# ControlBoard.net
KiCad netlist of a schematic drawn in EAGLE
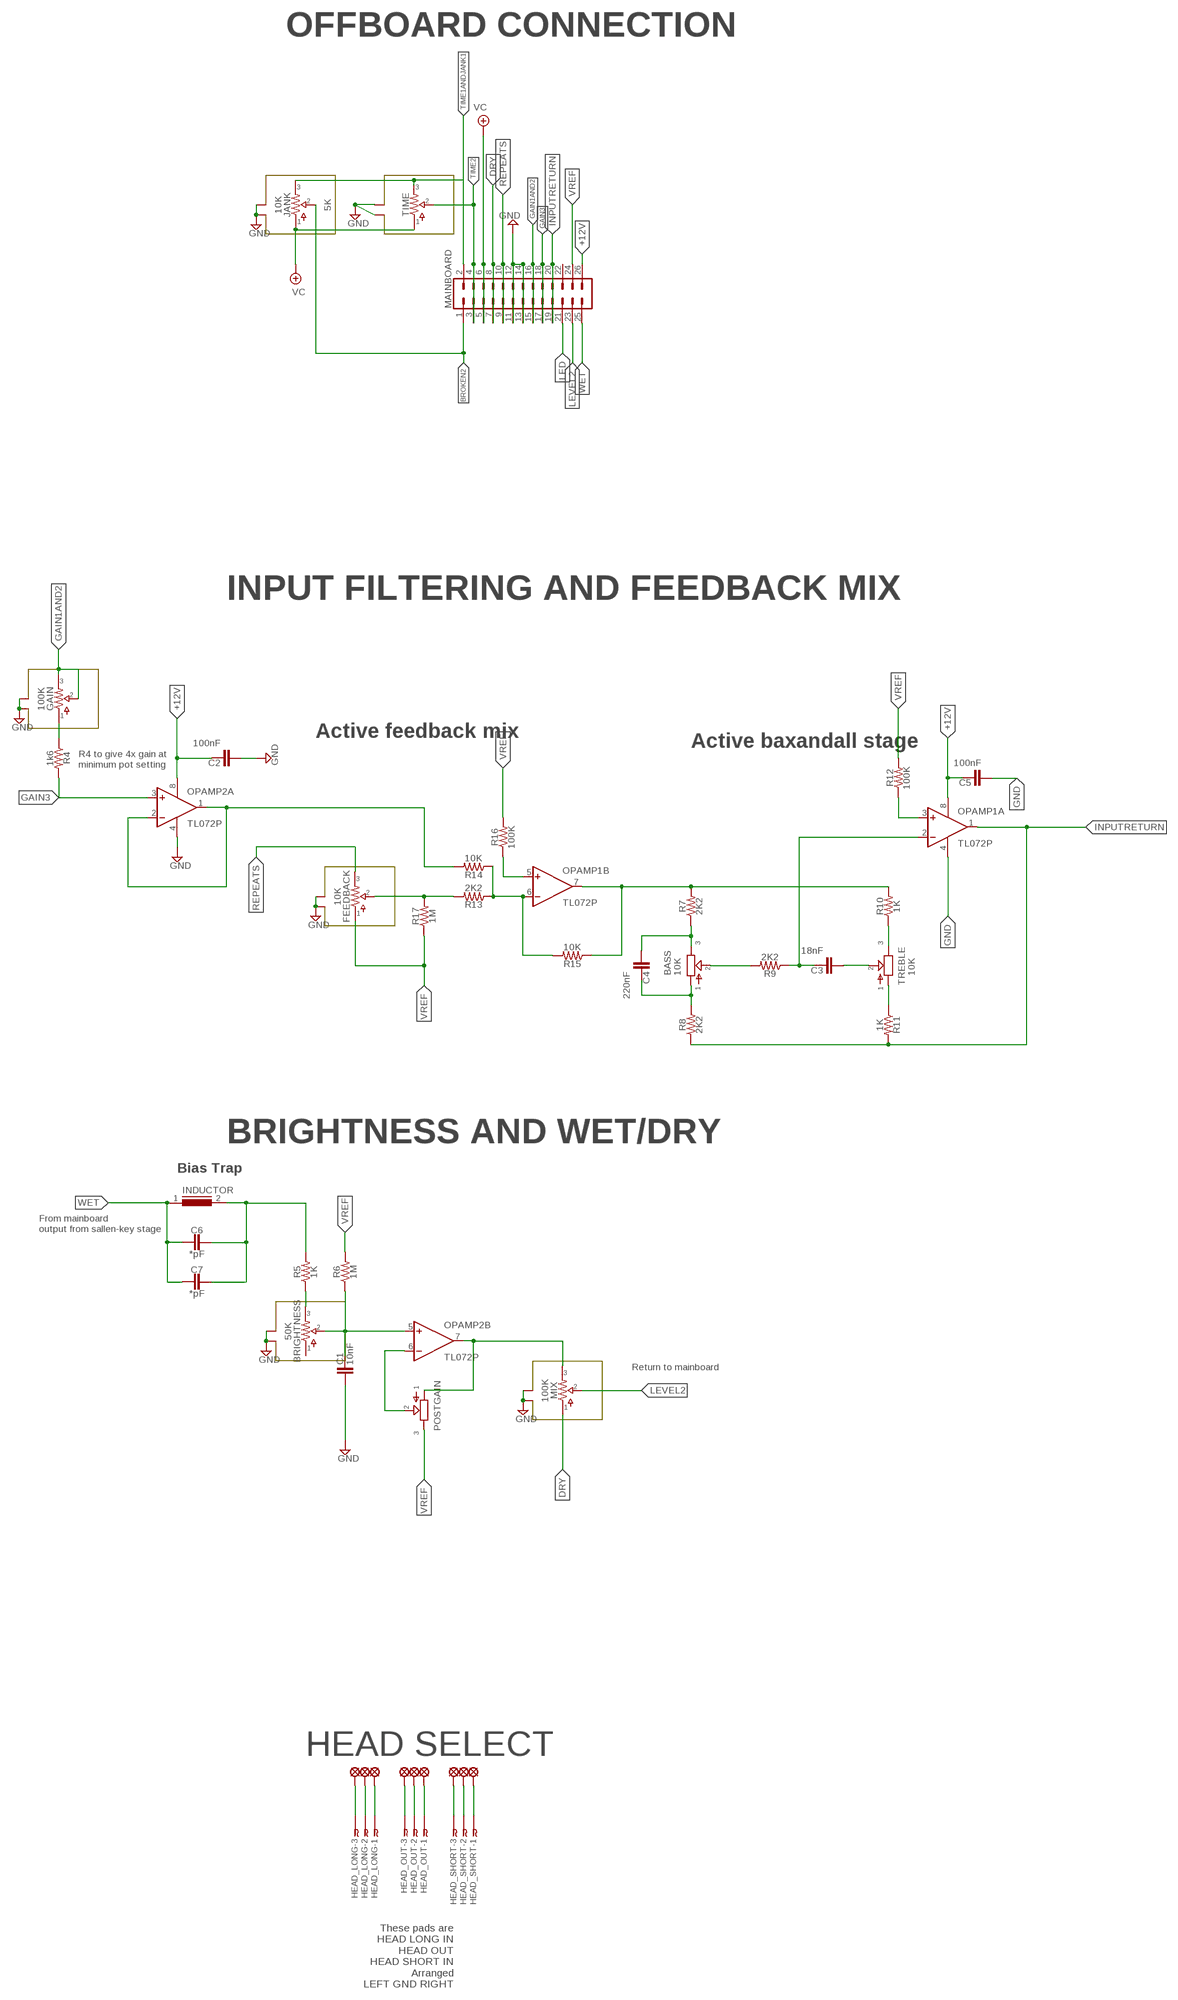
[diagram p0: schematic, sheet 1]

(export (version "E")
  (design (tool "Eeschema 10.0.6"))
  (components
    (comp (ref "BASS")
      (value "10K")
      (footprint "eagle-import:B375P")
      (libsource (lib "eagle-import") (part "POT-EU375"))
    )
    (comp (ref "BRIGHTNESS")
      (value "50K")
      (footprint "eagle-import:9MM_METAL_SHAFT")
      (libsource (lib "eagle-import") (part "9MM.1"))
    )
    (comp (ref "C1")
      (value "10nF")
      (footprint "eagle-import:.33UF+")
      (libsource (lib "eagle-import") (part "CAP.5"))
    )
    (comp (ref "C2")
      (value "100nF")
      (footprint "eagle-import:5MM")
      (libsource (lib "eagle-import") (part "CAP.2"))
    )
    (comp (ref "C3")
      (value "18nF")
      (footprint "eagle-import:.33UF+")
      (libsource (lib "eagle-import") (part "CAP.5"))
    )
    (comp (ref "C4")
      (value "220nF")
      (footprint "eagle-import:.33UF+")
      (libsource (lib "eagle-import") (part "CAP.5"))
    )
    (comp (ref "C5")
      (value "100nF")
      (footprint "eagle-import:5MM")
      (libsource (lib "eagle-import") (part "CAP.2"))
    )
    (comp (ref "C6")
      (value "*pF")
      (footprint "eagle-import:.33UF+")
      (libsource (lib "eagle-import") (part "CAP.5"))
    )
    (comp (ref "C7")
      (value "*pF")
      (footprint "eagle-import:.33UF+")
      (libsource (lib "eagle-import") (part "CAP.5"))
    )
    (comp (ref "FEEDBACK")
      (value "10K")
      (footprint "eagle-import:9MM_METAL_SHAFT")
      (libsource (lib "eagle-import") (part "9MM.1"))
    )
    (comp (ref "GAIN")
      (value "100K")
      (footprint "eagle-import:9MM_METAL_SHAFT")
      (libsource (lib "eagle-import") (part "9MM.1"))
    )
    (comp (ref "HEAD_LONG")
      (value "03-JST-B3B-XH-A")
      (footprint "eagle-import:B3B-XH")
      (libsource (lib "eagle-import") (part "03-JST-B3B-XH-A"))
    )
    (comp (ref "HEAD_OUT")
      (value "03-JST-B3B-XH-A")
      (footprint "eagle-import:B3B-XH")
      (libsource (lib "eagle-import") (part "03-JST-B3B-XH-A"))
    )
    (comp (ref "HEAD_SHORT")
      (value "03-JST-B3B-XH-A")
      (footprint "eagle-import:B3B-XH")
      (libsource (lib "eagle-import") (part "03-JST-B3B-XH-A"))
    )
    (comp (ref "HIN_1")
      (value "SE14")
      (footprint "eagle-import:SE14")
      (libsource (lib "eagle-import") (part "SE14"))
    )
    (comp (ref "HIN_2")
      (value "SE14")
      (footprint "eagle-import:SE14")
      (libsource (lib "eagle-import") (part "SE14"))
    )
    (comp (ref "HIN_3")
      (value "SE14")
      (footprint "eagle-import:SE14")
      (libsource (lib "eagle-import") (part "SE14"))
    )
    (comp (ref "HIN_4")
      (value "SE14")
      (footprint "eagle-import:SE14")
      (libsource (lib "eagle-import") (part "SE14"))
    )
    (comp (ref "HIN_5")
      (value "SE14")
      (footprint "eagle-import:SE14")
      (libsource (lib "eagle-import") (part "SE14"))
    )
    (comp (ref "HIN_6")
      (value "SE14")
      (footprint "eagle-import:SE14")
      (libsource (lib "eagle-import") (part "SE14"))
    )
    (comp (ref "HOUT_1")
      (value "SE14")
      (footprint "eagle-import:SE14")
      (libsource (lib "eagle-import") (part "SE14"))
    )
    (comp (ref "HOUT_2")
      (value "SE14")
      (footprint "eagle-import:SE14")
      (libsource (lib "eagle-import") (part "SE14"))
    )
    (comp (ref "HOUT_3")
      (value "SE14")
      (footprint "eagle-import:SE14")
      (libsource (lib "eagle-import") (part "SE14"))
    )
    (comp (ref "INDUCTOR")
      (value "82114R")
      (footprint "eagle-import:82114R")
      (libsource (lib "eagle-import") (part "82114R"))
    )
    (comp (ref "JANK")
      (value "10K")
      (footprint "eagle-import:9MM_METAL_SHAFT")
      (libsource (lib "eagle-import") (part "9MM.1"))
    )
    (comp (ref "MAINBOARD")
      (value "CONN_13X22X13")
      (footprint "eagle-import:2X13")
      (libsource (lib "eagle-import") (part "CONN_13X22X13"))
    )
    (comp (ref "MIX")
      (value "100K")
      (footprint "eagle-import:9MM_METAL_SHAFT")
      (libsource (lib "eagle-import") (part "9MM.1"))
    )
    (comp (ref "OPAMP1")
      (value "TL072P")
      (footprint "eagle-import:DIL08")
      (libsource (lib "eagle-import") (part "TL072P"))
    )
    (comp (ref "OPAMP2")
      (value "TL072P")
      (footprint "eagle-import:DIL08")
      (libsource (lib "eagle-import") (part "TL072P"))
    )
    (comp (ref "POSTGAIN")
      (value "POT-EU375")
      (footprint "eagle-import:B375P")
      (libsource (lib "eagle-import") (part "POT-EU375"))
    )
    (comp (ref "R4")
      (value "1k6")
      (footprint "eagle-import:7.5MM.2")
      (libsource (lib "eagle-import") (part "R.3B"))
    )
    (comp (ref "R5")
      (value "1K")
      (footprint "eagle-import:7.5MM.2")
      (libsource (lib "eagle-import") (part "R.3B"))
    )
    (comp (ref "R6")
      (value "1M")
      (footprint "eagle-import:7.5MM.2")
      (libsource (lib "eagle-import") (part "R.3B"))
    )
    (comp (ref "R7")
      (value "2K2")
      (footprint "eagle-import:7.5MM.2")
      (libsource (lib "eagle-import") (part "R.3B"))
    )
    (comp (ref "R8")
      (value "2K2")
      (footprint "eagle-import:7.5MM.2")
      (libsource (lib "eagle-import") (part "R.3B"))
    )
    (comp (ref "R9")
      (value "2K2")
      (footprint "eagle-import:7.5MM.2")
      (libsource (lib "eagle-import") (part "R.3B"))
    )
    (comp (ref "R10")
      (value "1K")
      (footprint "eagle-import:7.5MM.2")
      (libsource (lib "eagle-import") (part "R.3B"))
    )
    (comp (ref "R11")
      (value "1K")
      (footprint "eagle-import:7.5MM.2")
      (libsource (lib "eagle-import") (part "R.3B"))
    )
    (comp (ref "R12")
      (value "100K")
      (footprint "eagle-import:7.5MM.2")
      (libsource (lib "eagle-import") (part "R.3B"))
    )
    (comp (ref "R13")
      (value "2K2")
      (footprint "eagle-import:7.5MM.2")
      (libsource (lib "eagle-import") (part "R.3B"))
    )
    (comp (ref "R14")
      (value "10K")
      (footprint "eagle-import:7.5MM.2")
      (libsource (lib "eagle-import") (part "R.3B"))
    )
    (comp (ref "R15")
      (value "10K")
      (footprint "eagle-import:7.5MM.2")
      (libsource (lib "eagle-import") (part "R.3B"))
    )
    (comp (ref "R16")
      (value "100K")
      (footprint "eagle-import:7.5MM.2")
      (libsource (lib "eagle-import") (part "R.3B"))
    )
    (comp (ref "R17")
      (value "1M")
      (footprint "eagle-import:7.5MM.2")
      (libsource (lib "eagle-import") (part "R.3B"))
    )
    (comp (ref "TIME")
      (value "5K")
      (footprint "eagle-import:9MM_METAL_SHAFT")
      (libsource (lib "eagle-import") (part "9MM.1"))
    )
    (comp (ref "TREBLE")
      (value "10K")
      (footprint "eagle-import:B375P")
      (libsource (lib "eagle-import") (part "POT-EU375"))
    )
  )
  (nets
    (net (code "1") (name "+12V") (class "Default")
      (node (ref "C2") (pin "1") (pinfunction "1_1") (pintype "passive"))
      (node (ref "C5") (pin "1") (pinfunction "1_1") (pintype "passive"))
      (node (ref "MAINBOARD") (pin "26") (pinfunction "26_26") (pintype "passive"))
      (node (ref "OPAMP1") (pin "8") (pinfunction "V+_8") (pintype "power_in"))
      (node (ref "OPAMP2") (pin "8") (pinfunction "V+_8") (pintype "power_in"))
    )
    (net (code "2") (name "BROKEN2") (class "Default")
      (node (ref "JANK") (pin "P$2") (pinfunction "2_P$2") (pintype "passive"))
      (node (ref "MAINBOARD") (pin "1") (pinfunction "1_1") (pintype "passive"))
    )
    (net (code "3") (name "DRY") (class "Default")
      (node (ref "MAINBOARD") (pin "7") (pinfunction "7_7") (pintype "passive"))
      (node (ref "MAINBOARD") (pin "8") (pinfunction "8_8") (pintype "passive"))
      (node (ref "MIX") (pin "P$1") (pinfunction "1_P$1") (pintype "passive"))
    )
    (net (code "4") (name "GAIN1AND2") (class "Default")
      (node (ref "GAIN") (pin "P$2") (pinfunction "2_P$2") (pintype "passive"))
      (node (ref "GAIN") (pin "P$3") (pinfunction "3_P$3") (pintype "passive"))
      (node (ref "MAINBOARD") (pin "15") (pinfunction "15_15") (pintype "passive"))
      (node (ref "MAINBOARD") (pin "16") (pinfunction "16_16") (pintype "passive"))
    )
    (net (code "5") (name "GAIN3") (class "Default")
      (node (ref "MAINBOARD") (pin "17") (pinfunction "17_17") (pintype "passive"))
      (node (ref "MAINBOARD") (pin "18") (pinfunction "18_18") (pintype "passive"))
      (node (ref "OPAMP2") (pin "3") (pinfunction "+IN_3") (pintype "input"))
      (node (ref "R4") (pin "2") (pinfunction "2_2") (pintype "passive"))
    )
    (net (code "6") (name "GND") (class "Default")
      (node (ref "BRIGHTNESS") (pin "P$4") (pinfunction "CHAS$1_P$4") (pintype "bidirectional"))
      (node (ref "BRIGHTNESS") (pin "P$5") (pinfunction "CHAS$2_P$5") (pintype "bidirectional"))
      (node (ref "C1") (pin "2") (pinfunction "2_2") (pintype "passive"))
      (node (ref "C2") (pin "2") (pinfunction "2_2") (pintype "passive"))
      (node (ref "C5") (pin "2") (pinfunction "2_2") (pintype "passive"))
      (node (ref "FEEDBACK") (pin "P$4") (pinfunction "CHAS$1_P$4") (pintype "bidirectional"))
      (node (ref "FEEDBACK") (pin "P$5") (pinfunction "CHAS$2_P$5") (pintype "bidirectional"))
      (node (ref "GAIN") (pin "P$4") (pinfunction "CHAS$1_P$4") (pintype "bidirectional"))
      (node (ref "GAIN") (pin "P$5") (pinfunction "CHAS$2_P$5") (pintype "bidirectional"))
      (node (ref "JANK") (pin "P$4") (pinfunction "CHAS$1_P$4") (pintype "bidirectional"))
      (node (ref "JANK") (pin "P$5") (pinfunction "CHAS$2_P$5") (pintype "bidirectional"))
      (node (ref "MAINBOARD") (pin "11") (pinfunction "11_11") (pintype "passive"))
      (node (ref "MAINBOARD") (pin "12") (pinfunction "12_12") (pintype "passive"))
      (node (ref "MAINBOARD") (pin "13") (pinfunction "13_13") (pintype "passive"))
      (node (ref "MAINBOARD") (pin "14") (pinfunction "14_14") (pintype "passive"))
      (node (ref "MIX") (pin "P$4") (pinfunction "CHAS$1_P$4") (pintype "bidirectional"))
      (node (ref "MIX") (pin "P$5") (pinfunction "CHAS$2_P$5") (pintype "bidirectional"))
      (node (ref "OPAMP1") (pin "4") (pinfunction "V-_4") (pintype "power_in"))
      (node (ref "OPAMP2") (pin "4") (pinfunction "V-_4") (pintype "power_in"))
      (node (ref "TIME") (pin "P$4") (pinfunction "CHAS$1_P$4") (pintype "bidirectional"))
      (node (ref "TIME") (pin "P$5") (pinfunction "CHAS$2_P$5") (pintype "bidirectional"))
    )
    (net (code "7") (name "INPUTRETURN") (class "Default")
      (node (ref "MAINBOARD") (pin "19") (pinfunction "19_19") (pintype "passive"))
      (node (ref "MAINBOARD") (pin "20") (pinfunction "20_20") (pintype "passive"))
      (node (ref "OPAMP1") (pin "1") (pinfunction "OUT_1") (pintype "output"))
      (node (ref "R11") (pin "2") (pinfunction "2_2") (pintype "passive"))
      (node (ref "R8") (pin "1") (pinfunction "1_1") (pintype "passive"))
    )
    (net (code "8") (name "LED") (class "Default")
      (node (ref "MAINBOARD") (pin "21") (pinfunction "21_21") (pintype "passive"))
    )
    (net (code "9") (name "LEVEL2") (class "Default")
      (node (ref "MAINBOARD") (pin "23") (pinfunction "23_23") (pintype "passive"))
      (node (ref "MIX") (pin "P$2") (pinfunction "2_P$2") (pintype "passive"))
    )
    (net (code "10") (name "Net-(BASS-Pad1)") (class "Default")
      (node (ref "BASS") (pin "1") (pinfunction "1_1") (pintype "passive"))
      (node (ref "C4") (pin "1") (pinfunction "1_1") (pintype "passive"))
      (node (ref "R8") (pin "2") (pinfunction "2_2") (pintype "passive"))
    )
    (net (code "11") (name "Net-(BASS-Pad2)") (class "Default")
      (node (ref "BASS") (pin "2") (pinfunction "2_2") (pintype "passive"))
      (node (ref "R9") (pin "2") (pinfunction "2_2") (pintype "passive"))
    )
    (net (code "12") (name "Net-(BASS-Pad3)") (class "Default")
      (node (ref "BASS") (pin "3") (pinfunction "3_3") (pintype "passive"))
      (node (ref "C4") (pin "2") (pinfunction "2_2") (pintype "passive"))
      (node (ref "R7") (pin "1") (pinfunction "1_1") (pintype "passive"))
    )
    (net (code "13") (name "Net-(BRIGHTNESS-2)") (class "Default")
      (node (ref "BRIGHTNESS") (pin "P$2") (pinfunction "2_P$2") (pintype "passive"))
      (node (ref "C1") (pin "1") (pinfunction "1_1") (pintype "passive"))
      (node (ref "OPAMP2") (pin "5") (pinfunction "+IN_5") (pintype "input"))
      (node (ref "R6") (pin "1") (pinfunction "1_1") (pintype "passive"))
    )
    (net (code "14") (name "Net-(BRIGHTNESS-3)") (class "Default")
      (node (ref "BRIGHTNESS") (pin "P$3") (pinfunction "3_P$3") (pintype "passive"))
      (node (ref "R5") (pin "1") (pinfunction "1_1") (pintype "passive"))
    )
    (net (code "15") (name "Net-(C3-Pad2)") (class "Default")
      (node (ref "C3") (pin "2") (pinfunction "2_2") (pintype "passive"))
      (node (ref "TREBLE") (pin "2") (pinfunction "2_2") (pintype "passive"))
    )
    (net (code "16") (name "Net-(C6-Pad1)") (class "Default")
      (node (ref "C6") (pin "1") (pinfunction "1_1") (pintype "passive"))
      (node (ref "C7") (pin "1") (pinfunction "1_1") (pintype "passive"))
      (node (ref "INDUCTOR") (pin "2") (pinfunction "2_2") (pintype "passive"))
      (node (ref "R5") (pin "2") (pinfunction "2_2") (pintype "passive"))
    )
    (net (code "17") (name "Net-(FEEDBACK-2)") (class "Default")
      (node (ref "FEEDBACK") (pin "P$2") (pinfunction "2_P$2") (pintype "passive"))
      (node (ref "R13") (pin "2") (pinfunction "2_2") (pintype "passive"))
      (node (ref "R17") (pin "2") (pinfunction "2_2") (pintype "passive"))
    )
    (net (code "18") (name "Net-(GAIN-1)") (class "Default")
      (node (ref "GAIN") (pin "P$1") (pinfunction "1_P$1") (pintype "passive"))
      (node (ref "R4") (pin "1") (pinfunction "1_1") (pintype "passive"))
    )
    (net (code "19") (name "Net-(HEAD_LONGA-1)") (class "Default")
      (node (ref "HEAD_LONG") (pin "P$1") (pinfunction "1_P$1") (pintype "passive"))
      (node (ref "HIN_6") (pin "MP") (pinfunction "MP_MP") (pintype "passive"))
    )
    (net (code "20") (name "Net-(HEAD_LONGB-1)") (class "Default")
      (node (ref "HEAD_LONG") (pin "P$2") (pinfunction "1_P$2") (pintype "passive"))
      (node (ref "HIN_5") (pin "MP") (pinfunction "MP_MP") (pintype "passive"))
    )
    (net (code "21") (name "Net-(HEAD_LONGC-1)") (class "Default")
      (node (ref "HEAD_LONG") (pin "P$3") (pinfunction "1_P$3") (pintype "passive"))
      (node (ref "HIN_4") (pin "MP") (pinfunction "MP_MP") (pintype "passive"))
    )
    (net (code "22") (name "Net-(HEAD_OUTA-1)") (class "Default")
      (node (ref "HEAD_OUT") (pin "P$1") (pinfunction "1_P$1") (pintype "passive"))
      (node (ref "HOUT_3") (pin "MP") (pinfunction "MP_MP") (pintype "passive"))
    )
    (net (code "23") (name "Net-(HEAD_OUTB-1)") (class "Default")
      (node (ref "HEAD_OUT") (pin "P$2") (pinfunction "1_P$2") (pintype "passive"))
      (node (ref "HOUT_2") (pin "MP") (pinfunction "MP_MP") (pintype "passive"))
    )
    (net (code "24") (name "Net-(HEAD_OUTC-1)") (class "Default")
      (node (ref "HEAD_OUT") (pin "P$3") (pinfunction "1_P$3") (pintype "passive"))
      (node (ref "HOUT_1") (pin "MP") (pinfunction "MP_MP") (pintype "passive"))
    )
    (net (code "25") (name "Net-(HEAD_SHORTA-1)") (class "Default")
      (node (ref "HEAD_SHORT") (pin "P$1") (pinfunction "1_P$1") (pintype "passive"))
      (node (ref "HIN_3") (pin "MP") (pinfunction "MP_MP") (pintype "passive"))
    )
    (net (code "26") (name "Net-(HEAD_SHORTB-1)") (class "Default")
      (node (ref "HEAD_SHORT") (pin "P$2") (pinfunction "1_P$2") (pintype "passive"))
      (node (ref "HIN_2") (pin "MP") (pinfunction "MP_MP") (pintype "passive"))
    )
    (net (code "27") (name "Net-(HEAD_SHORTC-1)") (class "Default")
      (node (ref "HEAD_SHORT") (pin "P$3") (pinfunction "1_P$3") (pintype "passive"))
      (node (ref "HIN_1") (pin "MP") (pinfunction "MP_MP") (pintype "passive"))
    )
    (net (code "28") (name "Net-(MIX-3)") (class "Default")
      (node (ref "MIX") (pin "P$3") (pinfunction "3_P$3") (pintype "passive"))
      (node (ref "OPAMP2") (pin "7") (pinfunction "OUT_7") (pintype "output"))
      (node (ref "POSTGAIN") (pin "1") (pinfunction "1_1") (pintype "passive"))
    )
    (net (code "29") (name "Net-(OPAMP1A-+IN)") (class "Default")
      (node (ref "OPAMP1") (pin "3") (pinfunction "+IN_3") (pintype "input"))
      (node (ref "R12") (pin "1") (pinfunction "1_1") (pintype "passive"))
    )
    (net (code "30") (name "Net-(OPAMP1A--IN)") (class "Default")
      (node (ref "C3") (pin "1") (pinfunction "1_1") (pintype "passive"))
      (node (ref "OPAMP1") (pin "2") (pinfunction "-IN_2") (pintype "input"))
      (node (ref "R9") (pin "1") (pinfunction "1_1") (pintype "passive"))
    )
    (net (code "31") (name "Net-(OPAMP1B-+IN)") (class "Default")
      (node (ref "OPAMP1") (pin "5") (pinfunction "+IN_5") (pintype "input"))
      (node (ref "R16") (pin "1") (pinfunction "1_1") (pintype "passive"))
    )
    (net (code "32") (name "Net-(OPAMP1B--IN)") (class "Default")
      (node (ref "OPAMP1") (pin "6") (pinfunction "-IN_6") (pintype "input"))
      (node (ref "R13") (pin "1") (pinfunction "1_1") (pintype "passive"))
      (node (ref "R14") (pin "1") (pinfunction "1_1") (pintype "passive"))
      (node (ref "R15") (pin "2") (pinfunction "2_2") (pintype "passive"))
    )
    (net (code "33") (name "Net-(OPAMP1B-OUT)") (class "Default")
      (node (ref "OPAMP1") (pin "7") (pinfunction "OUT_7") (pintype "output"))
      (node (ref "R10") (pin "2") (pinfunction "2_2") (pintype "passive"))
      (node (ref "R15") (pin "1") (pinfunction "1_1") (pintype "passive"))
      (node (ref "R7") (pin "2") (pinfunction "2_2") (pintype "passive"))
    )
    (net (code "34") (name "Net-(OPAMP2A--IN)") (class "Default")
      (node (ref "OPAMP2") (pin "1") (pinfunction "OUT_1") (pintype "output"))
      (node (ref "OPAMP2") (pin "2") (pinfunction "-IN_2") (pintype "input"))
      (node (ref "R14") (pin "2") (pinfunction "2_2") (pintype "passive"))
    )
    (net (code "35") (name "Net-(OPAMP2B--IN)") (class "Default")
      (node (ref "OPAMP2") (pin "6") (pinfunction "-IN_6") (pintype "input"))
      (node (ref "POSTGAIN") (pin "2") (pinfunction "2_2") (pintype "passive"))
    )
    (net (code "36") (name "Net-(R10-Pad1)") (class "Default")
      (node (ref "R10") (pin "1") (pinfunction "1_1") (pintype "passive"))
      (node (ref "TREBLE") (pin "3") (pinfunction "3_3") (pintype "passive"))
    )
    (net (code "37") (name "Net-(R11-Pad1)") (class "Default")
      (node (ref "R11") (pin "1") (pinfunction "1_1") (pintype "passive"))
      (node (ref "TREBLE") (pin "1") (pinfunction "1_1") (pintype "passive"))
    )
    (net (code "38") (name "REPEATS") (class "Default")
      (node (ref "FEEDBACK") (pin "P$3") (pinfunction "3_P$3") (pintype "passive"))
      (node (ref "MAINBOARD") (pin "10") (pinfunction "10_10") (pintype "passive"))
      (node (ref "MAINBOARD") (pin "9") (pinfunction "9_9") (pintype "passive"))
    )
    (net (code "39") (name "TIME1ANDJANK1") (class "Default")
      (node (ref "JANK") (pin "P$3") (pinfunction "3_P$3") (pintype "passive"))
      (node (ref "MAINBOARD") (pin "2") (pinfunction "2_2") (pintype "passive"))
      (node (ref "TIME") (pin "P$3") (pinfunction "3_P$3") (pintype "passive"))
    )
    (net (code "40") (name "TIME2") (class "Default")
      (node (ref "MAINBOARD") (pin "3") (pinfunction "3_3") (pintype "passive"))
      (node (ref "MAINBOARD") (pin "4") (pinfunction "4_4") (pintype "passive"))
      (node (ref "TIME") (pin "P$2") (pinfunction "2_P$2") (pintype "passive"))
    )
    (net (code "41") (name "VC") (class "Default")
      (node (ref "JANK") (pin "P$1") (pinfunction "1_P$1") (pintype "passive"))
      (node (ref "MAINBOARD") (pin "5") (pinfunction "5_5") (pintype "passive"))
      (node (ref "MAINBOARD") (pin "6") (pinfunction "6_6") (pintype "passive"))
      (node (ref "TIME") (pin "P$1") (pinfunction "1_P$1") (pintype "passive"))
    )
    (net (code "42") (name "VREF") (class "Default")
      (node (ref "FEEDBACK") (pin "P$1") (pinfunction "1_P$1") (pintype "passive"))
      (node (ref "MAINBOARD") (pin "24") (pinfunction "24_24") (pintype "passive"))
      (node (ref "POSTGAIN") (pin "3") (pinfunction "3_3") (pintype "passive"))
      (node (ref "R12") (pin "2") (pinfunction "2_2") (pintype "passive"))
      (node (ref "R16") (pin "2") (pinfunction "2_2") (pintype "passive"))
      (node (ref "R17") (pin "1") (pinfunction "1_1") (pintype "passive"))
      (node (ref "R6") (pin "2") (pinfunction "2_2") (pintype "passive"))
    )
    (net (code "43") (name "WET") (class "Default")
      (node (ref "C6") (pin "2") (pinfunction "2_2") (pintype "passive"))
      (node (ref "C7") (pin "2") (pinfunction "2_2") (pintype "passive"))
      (node (ref "INDUCTOR") (pin "1") (pinfunction "1_1") (pintype "passive"))
      (node (ref "MAINBOARD") (pin "25") (pinfunction "25_25") (pintype "passive"))
    )
    (net (code "44") (name "unconnected-(BRIGHTNESS-1-PadP$1)") (class "Default")
      (node (ref "BRIGHTNESS") (pin "P$1") (pinfunction "1_P$1") (pintype "passive"))
    )
    (net (code "45") (name "unconnected-(MAINBOARD-Pad22)") (class "Default")
      (node (ref "MAINBOARD") (pin "22") (pinfunction "22_22") (pintype "passive"))
    )
  )
)
